# Capteurs.net
KiCad netlist of a schematic drawn in Altium Designer
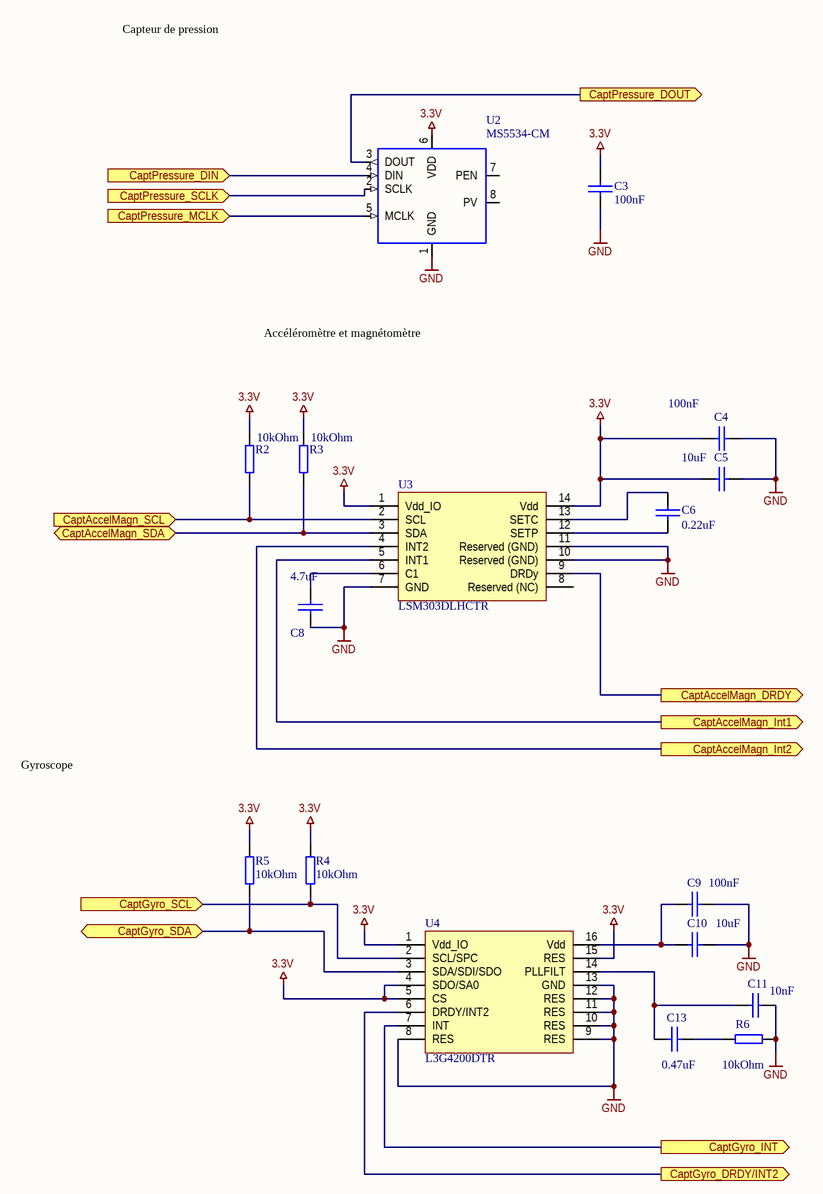
[diagram p0: Capteurs.SchDoc]

(export (version "E")
  (design (tool "Eeschema 10.0.6"))
  (components
    (comp (ref "C3")
      (value "100nF")
      (footprint "060301")
      (description "CAPA")
      (fields (field (name "Comment") "GRM188R71E104KA01D"))
      (libsource (lib "General-Sch-205") (part "CAPA"))
    )
    (comp (ref "C4")
      (value "100nF")
      (footprint "060301")
      (description "CAPA")
      (fields (field (name "Comment") "GRM188R71E104KA01D"))
      (libsource (lib "General-Sch-205") (part "CAPA"))
    )
    (comp (ref "C5")
      (value "10uF")
      (footprint "080501")
      (description "CAPA")
      (fields (field (name "Comment") "08056D106KAT2A"))
      (libsource (lib "General-Sch-205") (part "CAPA"))
    )
    (comp (ref "C6")
      (value "0.22uF")
      (footprint "120601")
      (description "CAPA")
      (fields (field (name "Comment") "UMK212F224ZD-T"))
      (libsource (lib "General-Sch-205") (part "CAPA"))
    )
    (comp (ref "C8")
      (value "4.7uF")
      (footprint "080501")
      (description "CAPA")
      (fields (field (name "Comment") "C0805C475K4PACTU"))
      (libsource (lib "General-Sch-205") (part "CAPA"))
    )
    (comp (ref "C9")
      (value "100nF")
      (footprint "060301")
      (description "CAPA")
      (fields (field (name "Comment") "GRM188R71E104KA01D"))
      (libsource (lib "General-Sch-205") (part "CAPA"))
    )
    (comp (ref "C10")
      (value "10uF")
      (footprint "080501")
      (description "CAPA")
      (fields (field (name "Comment") "08056D106KAT2A"))
      (libsource (lib "General-Sch-205") (part "CAPA"))
    )
    (comp (ref "C11")
      (value "10nF")
      (footprint "080501")
      (description "CAPA")
      (fields (field (name "Comment") "C0805C103K4RACTU"))
      (libsource (lib "General-Sch-205") (part "CAPA"))
    )
    (comp (ref "C13")
      (value "0.47uF")
      (footprint "060301")
      (description "CAPA")
      (fields (field (name "Comment") "C2012Y5V1H474Z/0.85"))
      (libsource (lib "General-Sch-205") (part "CAPA"))
    )
    (comp (ref "R2")
      (value "10kOhm")
      (footprint "080501")
      (fields (field (name "Comment") "ERJ-6GEYJ103V"))
      (libsource (lib "General-Sch-205") (part "RES"))
    )
    (comp (ref "R3")
      (value "10kOhm")
      (footprint "080501")
      (fields (field (name "Comment") "ERJ-6GEYJ103V"))
      (libsource (lib "General-Sch-205") (part "RES"))
    )
    (comp (ref "R4")
      (value "10kOhm")
      (footprint "080501")
      (fields (field (name "Comment") "ERJ-6GEYJ103V"))
      (libsource (lib "General-Sch-205") (part "RES"))
    )
    (comp (ref "R5")
      (value "10kOhm")
      (footprint "080501")
      (fields (field (name "Comment") "ERJ-6GEYJ103V"))
      (libsource (lib "General-Sch-205") (part "RES"))
    )
    (comp (ref "R6")
      (value "10kOhm")
      (footprint "080501")
      (fields (field (name "Comment") "ERJ-6GEYJ103V"))
      (libsource (lib "General-Sch-205") (part "RES"))
    )
    (comp (ref "U2")
      (value "MS5534-CM")
      (footprint "MS5534B")
      (description "Barometer Module")
      (libsource (lib "EISI") (part "MS5534B"))
    )
    (comp (ref "U3")
      (value "LSM303DLHCTR")
      (footprint "LGA-14L")
      (description "Accéléromètre et magnétomètre")
      (libsource (lib "Schlib1") (part "LSM303DLHC"))
    )
    (comp (ref "U4")
      (value "L3G4200DTR")
      (footprint "LGA-16")
      (description "Gyroscope")
      (libsource (lib "Schlib1") (part "L3G4200D"))
    )
  )
  (nets
    (net (code "1") (name "/CaptAccelMagn_DRDY") (class "Default")
      (node (ref "U3") (pin "9") (pinfunction "DRDy_9") (pintype "passive"))
    )
    (net (code "2") (name "/CaptAccelMagn_Int1") (class "Default")
      (node (ref "U3") (pin "5") (pinfunction "INT1_5") (pintype "passive"))
    )
    (net (code "3") (name "/CaptAccelMagn_Int2") (class "Default")
      (node (ref "U3") (pin "4") (pinfunction "INT2_4") (pintype "passive"))
    )
    (net (code "4") (name "/CaptAccelMagn_SCL") (class "Default")
      (node (ref "R2") (pin "1") (pintype "passive"))
      (node (ref "U3") (pin "2") (pinfunction "SCL_2") (pintype "passive"))
    )
    (net (code "5") (name "/CaptAccelMagn_SDA") (class "Default")
      (node (ref "R3") (pin "1") (pintype "passive"))
      (node (ref "U3") (pin "3") (pinfunction "SDA_3") (pintype "passive"))
    )
    (net (code "6") (name "/CaptGyro_DRDY{slash}INT2") (class "Default")
      (node (ref "U4") (pin "6") (pinfunction "DRDY/INT2_6") (pintype "passive"))
    )
    (net (code "7") (name "/CaptGyro_INT") (class "Default")
      (node (ref "U4") (pin "7") (pinfunction "INT_7") (pintype "passive"))
    )
    (net (code "8") (name "/CaptGyro_SCL") (class "Default")
      (node (ref "R4") (pin "1") (pintype "passive"))
      (node (ref "U4") (pin "2") (pinfunction "SCL/SPC_2") (pintype "passive"))
    )
    (net (code "9") (name "/CaptGyro_SDA") (class "Default")
      (node (ref "R5") (pin "1") (pintype "passive"))
      (node (ref "U4") (pin "3") (pinfunction "SDA/SDI/SDO_3") (pintype "passive"))
    )
    (net (code "10") (name "/CaptPressure_DIN") (class "Default")
      (node (ref "U2") (pin "4") (pinfunction "DIN_4") (pintype "input"))
    )
    (net (code "11") (name "/CaptPressure_DOUT") (class "Default")
      (node (ref "U2") (pin "3") (pinfunction "DOUT_3") (pintype "output"))
    )
    (net (code "12") (name "/CaptPressure_MCLK") (class "Default")
      (node (ref "U2") (pin "5") (pinfunction "MCLK_5") (pintype "input"))
    )
    (net (code "13") (name "/CaptPressure_SCLK") (class "Default")
      (node (ref "U2") (pin "2") (pinfunction "SCLK_2") (pintype "input"))
    )
    (net (code "14") (name "3.3V") (class "Default")
      (node (ref "C3") (pin "1") (pintype "passive"))
      (node (ref "C4") (pin "2") (pintype "passive"))
      (node (ref "C5") (pin "2") (pintype "passive"))
      (node (ref "R2") (pin "2") (pintype "passive"))
      (node (ref "R3") (pin "2") (pintype "passive"))
      (node (ref "R4") (pin "2") (pintype "passive"))
      (node (ref "R5") (pin "2") (pintype "passive"))
      (node (ref "U2") (pin "6") (pinfunction "VDD_6") (pintype "power_in"))
      (node (ref "U3") (pin "1") (pinfunction "Vdd_IO_1") (pintype "passive"))
      (node (ref "U3") (pin "14") (pinfunction "Vdd_14") (pintype "passive"))
      (node (ref "U4") (pin "1") (pinfunction "Vdd_IO_1") (pintype "passive"))
      (node (ref "U4") (pin "15") (pinfunction "RES_15") (pintype "passive"))
      (node (ref "U4") (pin "4") (pinfunction "SDO/SA0_4") (pintype "passive"))
      (node (ref "U4") (pin "5") (pinfunction "CS_5") (pintype "passive"))
    )
    (net (code "15") (name "GND") (class "Default")
      (node (ref "C10") (pin "1") (pintype "passive"))
      (node (ref "C11") (pin "1") (pintype "passive"))
      (node (ref "C3") (pin "2") (pintype "passive"))
      (node (ref "C4") (pin "1") (pintype "passive"))
      (node (ref "C5") (pin "1") (pintype "passive"))
      (node (ref "C8") (pin "2") (pintype "passive"))
      (node (ref "C9") (pin "1") (pintype "passive"))
      (node (ref "R6") (pin "2") (pintype "passive"))
      (node (ref "U2") (pin "1") (pinfunction "GND_1") (pintype "power_in"))
      (node (ref "U3") (pin "10") (pinfunction "Reserved_(GND)_10") (pintype "passive"))
      (node (ref "U3") (pin "11") (pinfunction "Reserved_(GND)_11") (pintype "passive"))
      (node (ref "U3") (pin "7") (pinfunction "GND_7") (pintype "passive"))
      (node (ref "U4") (pin "10") (pinfunction "RES_10") (pintype "passive"))
      (node (ref "U4") (pin "11") (pinfunction "RES_11") (pintype "passive"))
      (node (ref "U4") (pin "12") (pinfunction "RES_12") (pintype "passive"))
      (node (ref "U4") (pin "13") (pinfunction "GND_13") (pintype "passive"))
      (node (ref "U4") (pin "8") (pinfunction "RES_8") (pintype "passive"))
      (node (ref "U4") (pin "9") (pinfunction "RES_9") (pintype "passive"))
    )
    (net (code "16") (name "Net-(C13-Pad1)") (class "Default")
      (node (ref "C13") (pin "1") (pintype "passive"))
      (node (ref "R6") (pin "1") (pintype "passive"))
    )
    (net (code "17") (name "Net-(U3-C1)") (class "Default")
      (node (ref "C8") (pin "1") (pintype "passive"))
      (node (ref "U3") (pin "6") (pinfunction "C1_6") (pintype "passive"))
    )
    (net (code "18") (name "Net-(U3-SETC)") (class "Default")
      (node (ref "C6") (pin "2") (pintype "passive"))
      (node (ref "U3") (pin "13") (pinfunction "SETC_13") (pintype "passive"))
    )
    (net (code "19") (name "Net-(U3-SETP)") (class "Default")
      (node (ref "C6") (pin "1") (pintype "passive"))
      (node (ref "U3") (pin "12") (pinfunction "SETP_12") (pintype "passive"))
    )
    (net (code "20") (name "Net-(U4-PLLFILT)") (class "Default")
      (node (ref "C11") (pin "2") (pintype "passive"))
      (node (ref "C13") (pin "2") (pintype "passive"))
      (node (ref "U4") (pin "14") (pinfunction "PLLFILT_14") (pintype "passive"))
    )
    (net (code "21") (name "Net-(U4-Vdd)") (class "Default")
      (node (ref "C10") (pin "2") (pintype "passive"))
      (node (ref "C9") (pin "2") (pintype "passive"))
      (node (ref "U4") (pin "16") (pinfunction "Vdd_16") (pintype "passive"))
    )
    (net (code "22") (name "unconnected-(U2-PEN-Pad7)") (class "Default")
      (node (ref "U2") (pin "7") (pinfunction "PEN_7") (pintype "passive"))
    )
    (net (code "23") (name "unconnected-(U2-PV-Pad8)") (class "Default")
      (node (ref "U2") (pin "8") (pinfunction "PV_8") (pintype "passive"))
    )
    (net (code "24") (name "unconnected-(U3-Reserved_(NC)-Pad8)") (class "Default")
      (node (ref "U3") (pin "8") (pinfunction "Reserved_(NC)_8") (pintype "passive"))
    )
  )
)
